# 04_-_Current_Transformers.net
KiCad netlist of a schematic drawn in Altium Designer
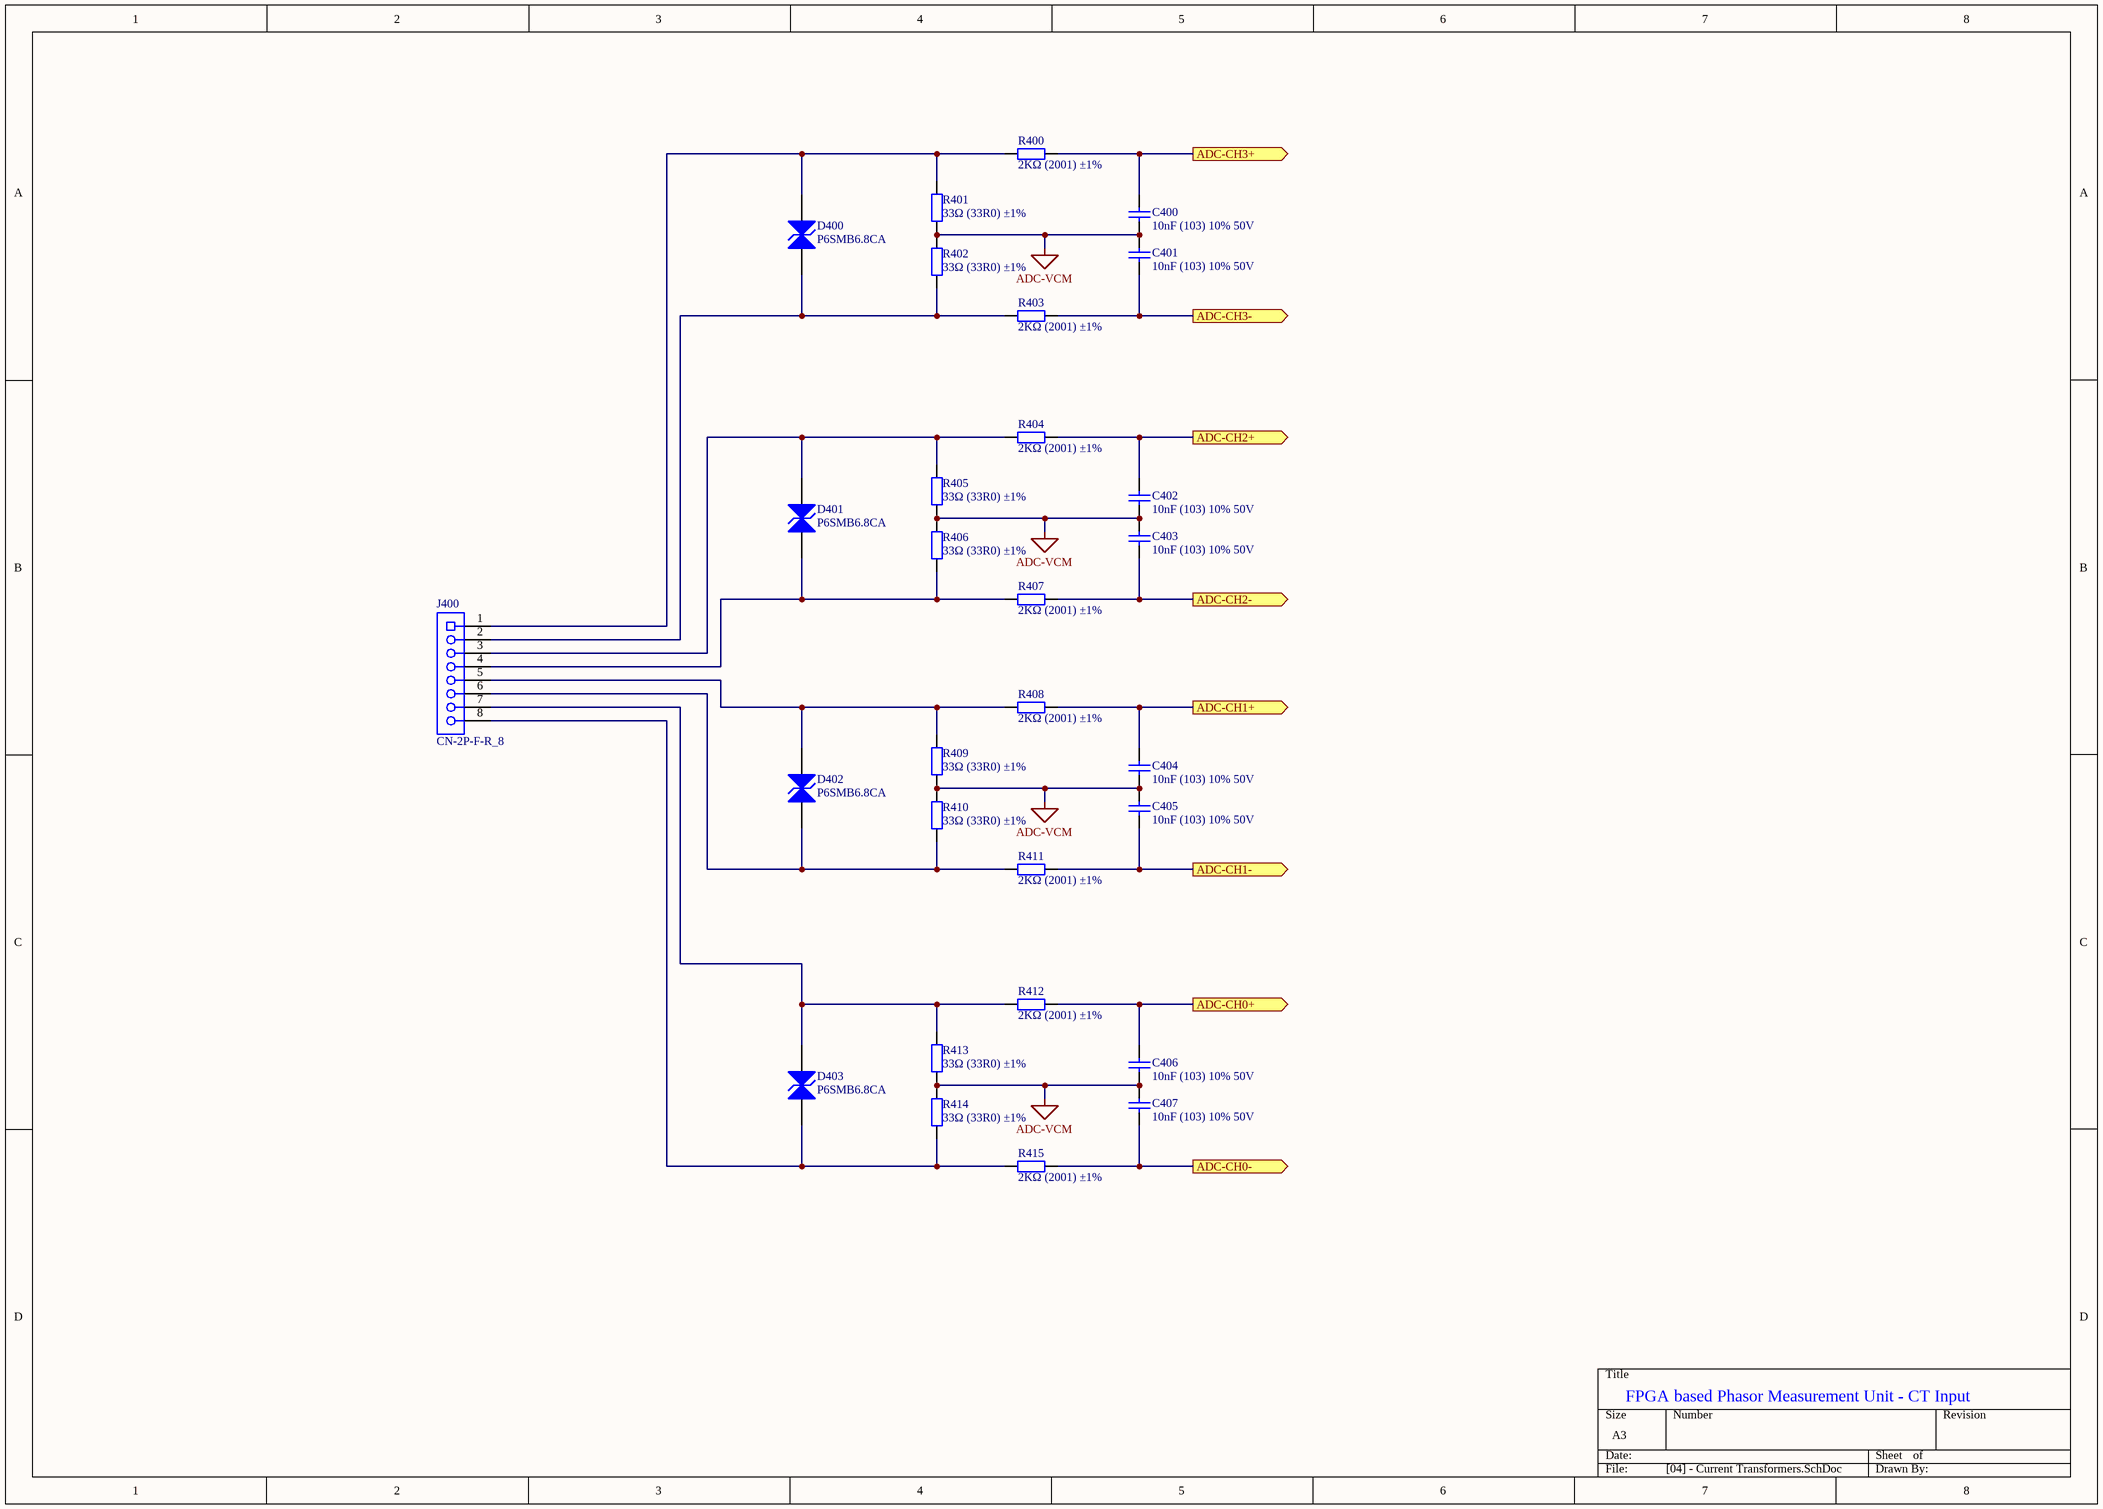
[diagram p0: [04] - Current Transformers.SchDoc]

(export (version "E")
  (design (tool "Eeschema 10.0.6"))
  (components
    (comp (ref "C400")
      (value "10nF (103) 10% 50V")
      (footprint "0805_C")
      (description "贴片电容")
      (libsource (lib "Cap") (part "0805 10nF (103) 10% 50V"))
    )
    (comp (ref "C401")
      (value "10nF (103) 10% 50V")
      (footprint "0805_C")
      (description "贴片电容")
      (libsource (lib "Cap") (part "0805 10nF (103) 10% 50V"))
    )
    (comp (ref "C402")
      (value "10nF (103) 10% 50V")
      (footprint "0805_C")
      (description "贴片电容")
      (libsource (lib "Cap") (part "0805 10nF (103) 10% 50V"))
    )
    (comp (ref "C403")
      (value "10nF (103) 10% 50V")
      (footprint "0805_C")
      (description "贴片电容")
      (libsource (lib "Cap") (part "0805 10nF (103) 10% 50V"))
    )
    (comp (ref "C404")
      (value "10nF (103) 10% 50V")
      (footprint "0805_C")
      (description "贴片电容")
      (libsource (lib "Cap") (part "0805 10nF (103) 10% 50V"))
    )
    (comp (ref "C405")
      (value "10nF (103) 10% 50V")
      (footprint "0805_C")
      (description "贴片电容")
      (libsource (lib "Cap") (part "0805 10nF (103) 10% 50V"))
    )
    (comp (ref "C406")
      (value "10nF (103) 10% 50V")
      (footprint "0805_C")
      (description "贴片电容")
      (libsource (lib "Cap") (part "0805 10nF (103) 10% 50V"))
    )
    (comp (ref "C407")
      (value "10nF (103) 10% 50V")
      (footprint "0805_C")
      (description "贴片电容")
      (libsource (lib "Cap") (part "0805 10nF (103) 10% 50V"))
    )
    (comp (ref "D400")
      (value "P6SMB6.8CA")
      (footprint "SMB(DO-214AA)_S1")
      (description "TVS")
      (libsource (lib "Diode") (part "SMB/DO-214AA P6SMB6.8CA"))
    )
    (comp (ref "D401")
      (value "P6SMB6.8CA")
      (footprint "SMB(DO-214AA)_S1")
      (description "TVS")
      (libsource (lib "Diode") (part "SMB/DO-214AA P6SMB6.8CA"))
    )
    (comp (ref "D402")
      (value "P6SMB6.8CA")
      (footprint "SMB(DO-214AA)_S1")
      (description "TVS")
      (libsource (lib "Diode") (part "SMB/DO-214AA P6SMB6.8CA"))
    )
    (comp (ref "D403")
      (value "P6SMB6.8CA")
      (footprint "SMB(DO-214AA)_S1")
      (description "TVS")
      (libsource (lib "Diode") (part "SMB/DO-214AA P6SMB6.8CA"))
    )
    (comp (ref "J400")
      (value "CN-2P-F-R_8")
      (footprint "PHOE-8way")
      (description "8way - 5.08 block")
      (libsource (lib "xPMU_lib") (part "CN-2P-F-R_8"))
    )
    (comp (ref "R400")
      (value "2KΩ (2001) ±1%")
      (footprint "0805_R")
      (description "贴片电阻")
      (libsource (lib "RES") (part "0805 2KΩ (2001) 1%"))
    )
    (comp (ref "R401")
      (value "33Ω (33R0) ±1%")
      (footprint "0603_R")
      (description "贴片电阻")
      (libsource (lib "RES") (part "0603 33Ω (33R0) 1%"))
    )
    (comp (ref "R402")
      (value "33Ω (33R0) ±1%")
      (footprint "0603_R")
      (description "贴片电阻")
      (libsource (lib "RES") (part "0603 33Ω (33R0) 1%"))
    )
    (comp (ref "R403")
      (value "2KΩ (2001) ±1%")
      (footprint "0805_R")
      (description "贴片电阻")
      (libsource (lib "RES") (part "0805 2KΩ (2001) 1%"))
    )
    (comp (ref "R404")
      (value "2KΩ (2001) ±1%")
      (footprint "0805_R")
      (description "贴片电阻")
      (libsource (lib "RES") (part "0805 2KΩ (2001) 1%"))
    )
    (comp (ref "R405")
      (value "33Ω (33R0) ±1%")
      (footprint "0603_R")
      (description "贴片电阻")
      (libsource (lib "RES") (part "0603 33Ω (33R0) 1%"))
    )
    (comp (ref "R406")
      (value "33Ω (33R0) ±1%")
      (footprint "0603_R")
      (description "贴片电阻")
      (libsource (lib "RES") (part "0603 33Ω (33R0) 1%"))
    )
    (comp (ref "R407")
      (value "2KΩ (2001) ±1%")
      (footprint "0805_R")
      (description "贴片电阻")
      (libsource (lib "RES") (part "0805 2KΩ (2001) 1%"))
    )
    (comp (ref "R408")
      (value "2KΩ (2001) ±1%")
      (footprint "0805_R")
      (description "贴片电阻")
      (libsource (lib "RES") (part "0805 2KΩ (2001) 1%"))
    )
    (comp (ref "R409")
      (value "33Ω (33R0) ±1%")
      (footprint "0603_R")
      (description "贴片电阻")
      (libsource (lib "RES") (part "0603 33Ω (33R0) 1%"))
    )
    (comp (ref "R410")
      (value "33Ω (33R0) ±1%")
      (footprint "0603_R")
      (description "贴片电阻")
      (libsource (lib "RES") (part "0603 33Ω (33R0) 1%"))
    )
    (comp (ref "R411")
      (value "2KΩ (2001) ±1%")
      (footprint "0805_R")
      (description "贴片电阻")
      (libsource (lib "RES") (part "0805 2KΩ (2001) 1%"))
    )
    (comp (ref "R412")
      (value "2KΩ (2001) ±1%")
      (footprint "0805_R")
      (description "贴片电阻")
      (libsource (lib "RES") (part "0805 2KΩ (2001) 1%"))
    )
    (comp (ref "R413")
      (value "33Ω (33R0) ±1%")
      (footprint "0603_R")
      (description "贴片电阻")
      (libsource (lib "RES") (part "0603 33Ω (33R0) 1%"))
    )
    (comp (ref "R414")
      (value "33Ω (33R0) ±1%")
      (footprint "0603_R")
      (description "贴片电阻")
      (libsource (lib "RES") (part "0603 33Ω (33R0) 1%"))
    )
    (comp (ref "R415")
      (value "2KΩ (2001) ±1%")
      (footprint "0805_R")
      (description "贴片电阻")
      (libsource (lib "RES") (part "0805 2KΩ (2001) 1%"))
    )
  )
  (nets
    (net (code "1") (name "/ADC-CH0+") (class "Default")
      (node (ref "C406") (pin "2") (pinfunction "2_2") (pintype "passive"))
      (node (ref "R412") (pin "1") (pinfunction "1_1") (pintype "passive"))
    )
    (net (code "2") (name "/ADC-CH0-") (class "Default")
      (node (ref "C407") (pin "1") (pinfunction "1_1") (pintype "passive"))
      (node (ref "R415") (pin "1") (pinfunction "1_1") (pintype "passive"))
    )
    (net (code "3") (name "/ADC-CH1+") (class "Default")
      (node (ref "C404") (pin "2") (pinfunction "2_2") (pintype "passive"))
      (node (ref "R408") (pin "1") (pinfunction "1_1") (pintype "passive"))
    )
    (net (code "4") (name "/ADC-CH1-") (class "Default")
      (node (ref "C405") (pin "1") (pinfunction "1_1") (pintype "passive"))
      (node (ref "R411") (pin "1") (pinfunction "1_1") (pintype "passive"))
    )
    (net (code "5") (name "/ADC-CH2+") (class "Default")
      (node (ref "C402") (pin "2") (pinfunction "2_2") (pintype "passive"))
      (node (ref "R404") (pin "1") (pinfunction "1_1") (pintype "passive"))
    )
    (net (code "6") (name "/ADC-CH2-") (class "Default")
      (node (ref "C403") (pin "1") (pinfunction "1_1") (pintype "passive"))
      (node (ref "R407") (pin "1") (pinfunction "1_1") (pintype "passive"))
    )
    (net (code "7") (name "/ADC-CH3+") (class "Default")
      (node (ref "C400") (pin "2") (pinfunction "2_2") (pintype "passive"))
      (node (ref "R400") (pin "1") (pinfunction "1_1") (pintype "passive"))
    )
    (net (code "8") (name "/ADC-CH3-") (class "Default")
      (node (ref "C401") (pin "1") (pinfunction "1_1") (pintype "passive"))
      (node (ref "R403") (pin "1") (pinfunction "1_1") (pintype "passive"))
    )
    (net (code "9") (name "ADC-VCM") (class "Default")
      (node (ref "C400") (pin "1") (pinfunction "1_1") (pintype "passive"))
      (node (ref "C401") (pin "2") (pinfunction "2_2") (pintype "passive"))
      (node (ref "C402") (pin "1") (pinfunction "1_1") (pintype "passive"))
      (node (ref "C403") (pin "2") (pinfunction "2_2") (pintype "passive"))
      (node (ref "C404") (pin "1") (pinfunction "1_1") (pintype "passive"))
      (node (ref "C405") (pin "2") (pinfunction "2_2") (pintype "passive"))
      (node (ref "C406") (pin "1") (pinfunction "1_1") (pintype "passive"))
      (node (ref "C407") (pin "2") (pinfunction "2_2") (pintype "passive"))
      (node (ref "R401") (pin "1") (pinfunction "1_1") (pintype "passive"))
      (node (ref "R402") (pin "2") (pinfunction "2_2") (pintype "passive"))
      (node (ref "R405") (pin "1") (pinfunction "1_1") (pintype "passive"))
      (node (ref "R406") (pin "2") (pinfunction "2_2") (pintype "passive"))
      (node (ref "R409") (pin "1") (pinfunction "1_1") (pintype "passive"))
      (node (ref "R410") (pin "2") (pinfunction "2_2") (pintype "passive"))
      (node (ref "R413") (pin "1") (pinfunction "1_1") (pintype "passive"))
      (node (ref "R414") (pin "2") (pinfunction "2_2") (pintype "passive"))
    )
    (net (code "10") (name "Net-(D400-A)") (class "Default")
      (node (ref "D400") (pin "1") (pinfunction "A_1") (pintype "passive"))
      (node (ref "J400") (pin "2") (pinfunction "2_2") (pintype "passive"))
      (node (ref "R402") (pin "1") (pinfunction "1_1") (pintype "passive"))
      (node (ref "R403") (pin "2") (pinfunction "2_2") (pintype "passive"))
    )
    (net (code "11") (name "Net-(D400-K)") (class "Default")
      (node (ref "D400") (pin "2") (pinfunction "K_2") (pintype "passive"))
      (node (ref "J400") (pin "1") (pinfunction "1_1") (pintype "passive"))
      (node (ref "R400") (pin "2") (pinfunction "2_2") (pintype "passive"))
      (node (ref "R401") (pin "2") (pinfunction "2_2") (pintype "passive"))
    )
    (net (code "12") (name "Net-(D401-A)") (class "Default")
      (node (ref "D401") (pin "1") (pinfunction "A_1") (pintype "passive"))
      (node (ref "J400") (pin "4") (pinfunction "4_4") (pintype "passive"))
      (node (ref "R406") (pin "1") (pinfunction "1_1") (pintype "passive"))
      (node (ref "R407") (pin "2") (pinfunction "2_2") (pintype "passive"))
    )
    (net (code "13") (name "Net-(D401-K)") (class "Default")
      (node (ref "D401") (pin "2") (pinfunction "K_2") (pintype "passive"))
      (node (ref "J400") (pin "3") (pinfunction "3_3") (pintype "passive"))
      (node (ref "R404") (pin "2") (pinfunction "2_2") (pintype "passive"))
      (node (ref "R405") (pin "2") (pinfunction "2_2") (pintype "passive"))
    )
    (net (code "14") (name "Net-(D402-A)") (class "Default")
      (node (ref "D402") (pin "1") (pinfunction "A_1") (pintype "passive"))
      (node (ref "J400") (pin "6") (pinfunction "6_6") (pintype "passive"))
      (node (ref "R410") (pin "1") (pinfunction "1_1") (pintype "passive"))
      (node (ref "R411") (pin "2") (pinfunction "2_2") (pintype "passive"))
    )
    (net (code "15") (name "Net-(D402-K)") (class "Default")
      (node (ref "D402") (pin "2") (pinfunction "K_2") (pintype "passive"))
      (node (ref "J400") (pin "5") (pinfunction "5_5") (pintype "passive"))
      (node (ref "R408") (pin "2") (pinfunction "2_2") (pintype "passive"))
      (node (ref "R409") (pin "2") (pinfunction "2_2") (pintype "passive"))
    )
    (net (code "16") (name "Net-(D403-A)") (class "Default")
      (node (ref "D403") (pin "1") (pinfunction "A_1") (pintype "passive"))
      (node (ref "J400") (pin "8") (pinfunction "8_8") (pintype "passive"))
      (node (ref "R414") (pin "1") (pinfunction "1_1") (pintype "passive"))
      (node (ref "R415") (pin "2") (pinfunction "2_2") (pintype "passive"))
    )
    (net (code "17") (name "Net-(D403-K)") (class "Default")
      (node (ref "D403") (pin "2") (pinfunction "K_2") (pintype "passive"))
      (node (ref "J400") (pin "7") (pinfunction "7_7") (pintype "passive"))
      (node (ref "R412") (pin "2") (pinfunction "2_2") (pintype "passive"))
      (node (ref "R413") (pin "2") (pinfunction "2_2") (pintype "passive"))
    )
  )
)
